# CONTROLLER_SCH.net
KiCad netlist of a schematic drawn in Altium Designer
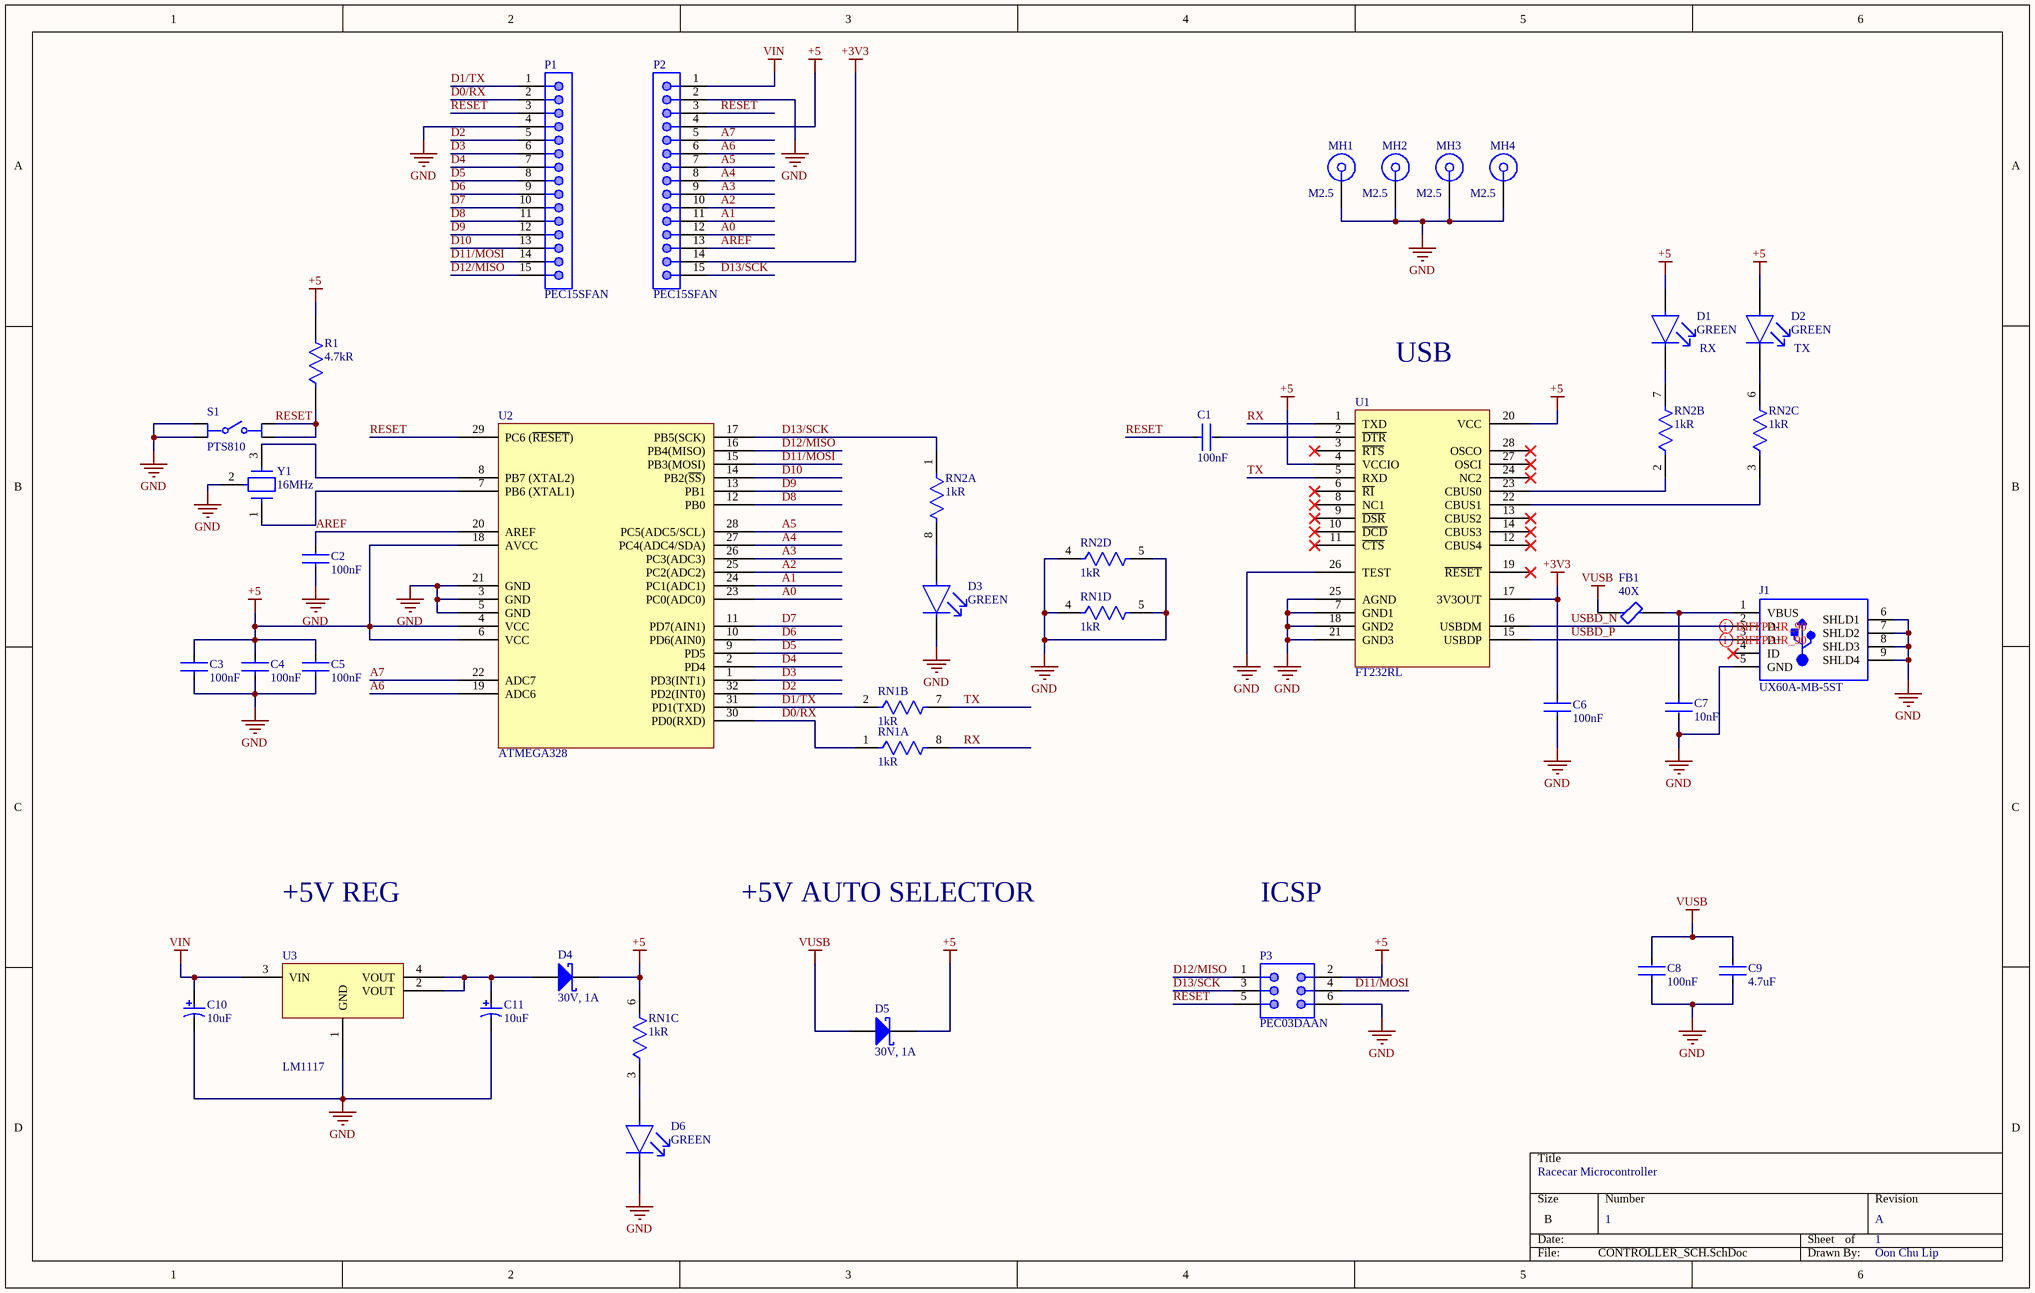
[diagram p0: CONTROLLER_SCH.SchDoc]

(export (version "E")
  (design (tool "Eeschema 10.0.6"))
  (components
    (comp (ref "C1")
      (value "100nF")
      (footprint "CAP_0603_TDK_CGA3")
      (description "±10% 50V Ceramic Capacitor X7R 0603 (1608 Metric)")
      (fields
        (field (name "MANUFACTURER") "TDK Corporation")
        (field (name "MANUFACTURER PART NUMBER") "CGA3E2X7R1H104K080AA")
      )
      (libsource (lib "CONTROLLER_INT_LIB") (part "CAP_100nF_10%_50V"))
    )
    (comp (ref "C2")
      (value "100nF")
      (footprint "CAP_0603_TDK_CGA3")
      (description "±10% 50V Ceramic Capacitor X7R 0603 (1608 Metric)")
      (fields
        (field (name "MANUFACTURER") "TDK Corporation")
        (field (name "MANUFACTURER PART NUMBER") "CGA3E2X7R1H104K080AA")
      )
      (libsource (lib "CONTROLLER_INT_LIB") (part "CAP_100nF_10%_50V"))
    )
    (comp (ref "C3")
      (value "100nF")
      (footprint "CAP_0603_TDK_CGA3")
      (description "±10% 50V Ceramic Capacitor X7R 0603 (1608 Metric)")
      (fields
        (field (name "MANUFACTURER") "TDK Corporation")
        (field (name "MANUFACTURER PART NUMBER") "CGA3E2X7R1H104K080AA")
      )
      (libsource (lib "CONTROLLER_INT_LIB") (part "CAP_100nF_10%_50V"))
    )
    (comp (ref "C4")
      (value "100nF")
      (footprint "CAP_0603_TDK_CGA3")
      (description "±10% 50V Ceramic Capacitor X7R 0603 (1608 Metric)")
      (fields
        (field (name "MANUFACTURER") "TDK Corporation")
        (field (name "MANUFACTURER PART NUMBER") "CGA3E2X7R1H104K080AA")
      )
      (libsource (lib "CONTROLLER_INT_LIB") (part "CAP_100nF_10%_50V"))
    )
    (comp (ref "C5")
      (value "100nF")
      (footprint "CAP_0603_TDK_CGA3")
      (description "±10% 50V Ceramic Capacitor X7R 0603 (1608 Metric)")
      (fields
        (field (name "MANUFACTURER") "TDK Corporation")
        (field (name "MANUFACTURER PART NUMBER") "CGA3E2X7R1H104K080AA")
      )
      (libsource (lib "CONTROLLER_INT_LIB") (part "CAP_100nF_10%_50V"))
    )
    (comp (ref "C6")
      (value "100nF")
      (footprint "CAP_0603_TDK_CGA3")
      (description "±10% 50V Ceramic Capacitor X7R 0603 (1608 Metric)")
      (fields
        (field (name "MANUFACTURER") "TDK Corporation")
        (field (name "MANUFACTURER PART NUMBER") "CGA3E2X7R1H104K080AA")
      )
      (libsource (lib "CONTROLLER_INT_LIB") (part "CAP_100nF_10%_50V"))
    )
    (comp (ref "C7")
      (value "10nF")
      (footprint "CAP_0603_MRT_GCM")
      (description "±10% 100V Ceramic Capacitor X7R 0603 (1608 Metric)")
      (fields
        (field (name "MANUFACTURER") "Murata Electronics")
        (field (name "MANUFACTURER PART NUMBER") "GCM188R72A103KA37D")
      )
      (libsource (lib "CONTROLLER_INT_LIB") (part "CAP_10nF_10%_100V"))
    )
    (comp (ref "C8")
      (value "100nF")
      (footprint "CAP_0603_TDK_CGA3")
      (description "±10% 50V Ceramic Capacitor X7R 0603 (1608 Metric)")
      (fields
        (field (name "MANUFACTURER") "TDK Corporation")
        (field (name "MANUFACTURER PART NUMBER") "CGA3E2X7R1H104K080AA")
      )
      (libsource (lib "CONTROLLER_INT_LIB") (part "CAP_100nF_10%_50V"))
    )
    (comp (ref "C9")
      (value "4.7uF")
      (footprint "CAP_0603_MRT_GRT")
      (description "±10% 25V Ceramic Capacitor X5R 0603 (1608 Metric)")
      (fields
        (field (name "MANUFACTURER") "Murata Electronics")
        (field (name "MANUFACTURER PART NUMBER") "GRT188R61E475KE13D")
      )
      (libsource (lib "CONTROLLER_INT_LIB") (part "CAP_4.7uF_10%_25V"))
    )
    (comp (ref "C10")
      (value "10uF")
      (footprint "PCAP_1411_VSH_TR3B")
      (description "Molded Tantalum Capacitors 1411 (3528 Metric) 1.1Ohm")
      (fields
        (field (name "MANUFACTURER") "Vishay Sprague")
        (field (name "MANUFACTURER PART NUMBER") "TR3B106K025C1100")
      )
      (libsource (lib "CONTROLLER_INT_LIB") (part "PCAP_10uF_10%_25V"))
    )
    (comp (ref "C11")
      (value "10uF")
      (footprint "PCAP_1411_VSH_TR3B")
      (description "Molded Tantalum Capacitors 1411 (3528 Metric) 1.1Ohm")
      (fields
        (field (name "MANUFACTURER") "Vishay Sprague")
        (field (name "MANUFACTURER PART NUMBER") "TR3B106K025C1100")
      )
      (libsource (lib "CONTROLLER_INT_LIB") (part "PCAP_10uF_10%_25V"))
    )
    (comp (ref "D1")
      (value "GREEN")
      (footprint "DIO_LED_GREEN_1608_APT1608")
      (description "Green 570nm LED Indication - Discrete 2.1V 0603 (1608 Metric)")
      (fields
        (field (name "MANUFACTURER") "Kingbright")
        (field (name "MANUFACTURER PART NUMBER") "APT1608CGCK")
      )
      (libsource (lib "CONTROLLER_INT_LIB") (part "DIO_LED_GREEN"))
    )
    (comp (ref "D2")
      (value "GREEN")
      (footprint "DIO_LED_GREEN_1608_APT1608")
      (description "Green 570nm LED Indication - Discrete 2.1V 0603 (1608 Metric)")
      (fields
        (field (name "MANUFACTURER") "Kingbright")
        (field (name "MANUFACTURER PART NUMBER") "APT1608CGCK")
      )
      (libsource (lib "CONTROLLER_INT_LIB") (part "DIO_LED_GREEN"))
    )
    (comp (ref "D3")
      (value "GREEN")
      (footprint "DIO_LED_GREEN_1608_APT1608")
      (description "Green 570nm LED Indication - Discrete 2.1V 0603 (1608 Metric)")
      (fields
        (field (name "MANUFACTURER") "Kingbright")
        (field (name "MANUFACTURER PART NUMBER") "APT1608CGCK")
      )
      (libsource (lib "CONTROLLER_INT_LIB") (part "DIO_LED_GREEN"))
    )
    (comp (ref "D4")
      (value "30V, 1A")
      (footprint "DIO_SCHOTTKY_DO_219AP")
      (description "Diode Schottky 1A Surface Mount MicroSMP (DO-219AD)")
      (fields
        (field (name "MANUFACTURER") "Vishay General Semiconductor - Diodes Division")
        (field (name "MANUFACTURER PART NUMBER") "MSS1P3L-M3/89A")
      )
      (libsource (lib "CONTROLLER_INT_LIB") (part "DIO_SCHOTTKY_30V_1A"))
    )
    (comp (ref "D5")
      (value "30V, 1A")
      (footprint "DIO_SCHOTTKY_DO_219AP")
      (description "Diode Schottky 1A Surface Mount MicroSMP (DO-219AD)")
      (fields
        (field (name "MANUFACTURER") "Vishay General Semiconductor - Diodes Division")
        (field (name "MANUFACTURER PART NUMBER") "MSS1P3L-M3/89A")
      )
      (libsource (lib "CONTROLLER_INT_LIB") (part "DIO_SCHOTTKY_30V_1A"))
    )
    (comp (ref "D6")
      (value "GREEN")
      (footprint "DIO_LED_GREEN_1608_APT1608")
      (description "Green 570nm LED Indication - Discrete 2.1V 0603 (1608 Metric)")
      (fields
        (field (name "MANUFACTURER") "Kingbright")
        (field (name "MANUFACTURER PART NUMBER") "APT1608CGCK")
      )
      (libsource (lib "CONTROLLER_INT_LIB") (part "DIO_LED_GREEN"))
    )
    (comp (ref "FB1")
      (value "40X")
      (footprint "FERRITE_0805_LRD_MI")
      (description "Power Line Ferrite Bead 0805 (2012 Metric) 1.5A 50mOhm")
      (fields
        (field (name "MANUFACTURER") "Laird-Signal Integrity Products")
        (field (name "MANUFACTURER PART NUMBER") "MI0805K400R-10")
      )
      (libsource (lib "CONTROLLER_INT_LIB") (part "FERRITE_40X_1.5A"))
    )
    (comp (ref "J1")
      (value "UX60A-MB-5ST")
      (footprint "CONN_USB_MINIB_FEMALE_SMD_RA")
      (description "USB - mini B USB 2.0 Receptacle Connector 5 Position Surface Mount, Right Angle")
      (fields (field (name "MANUFACTURER") "Hirose Electric Co LtdInc."))
      (libsource (lib "CONTROLLER_INT_LIB") (part "CONN_USB_MINIB_FEMALE_SMD_RA"))
    )
    (comp (ref "MH1")
      (value "M2.5")
      (footprint "MH_M2.5")
      (description "M2.5 Mounting Hole")
      (libsource (lib "CONTROLLER_INT_LIB") (part "MH_M2.5"))
    )
    (comp (ref "MH2")
      (value "M2.5")
      (footprint "MH_M2.5")
      (description "M2.5 Mounting Hole")
      (libsource (lib "CONTROLLER_INT_LIB") (part "MH_M2.5"))
    )
    (comp (ref "MH3")
      (value "M2.5")
      (footprint "MH_M2.5")
      (description "M2.5 Mounting Hole")
      (libsource (lib "CONTROLLER_INT_LIB") (part "MH_M2.5"))
    )
    (comp (ref "MH4")
      (value "M2.5")
      (footprint "MH_M2.5")
      (description "M2.5 Mounting Hole")
      (libsource (lib "CONTROLLER_INT_LIB") (part "MH_M2.5"))
    )
    (comp (ref "P1")
      (value "PEC15SFAN")
      (footprint "CONN_HEADER_MALE_0.1_1x15")
      (description "Connector Header Through Hole 15 position 0.100\" (2.54mm)")
      (fields (field (name "MANUFACTURER") "Sullins Connector Solutions"))
      (libsource (lib "") (part "CONN_VERT_HEADER_MALE_0.1_1x15_1"))
    )
    (comp (ref "P2")
      (value "PEC15SFAN")
      (footprint "CONN_HEADER_MALE_0.1_1x15")
      (description "Connector Header Through Hole 15 position 0.100\" (2.54mm)")
      (fields (field (name "MANUFACTURER") "Sullins Connector Solutions"))
      (libsource (lib "CONTROLLER_INT_LIB") (part "CONN_VERT_HEADER_MALE_0.1_1x15"))
    )
    (comp (ref "P3")
      (value "PEC03DAAN")
      (footprint "CONN_HEADER_MALE_0.1_2x3")
      (description "Connector Header Through Hole 6 position 0.100\" (2.54mm)")
      (fields (field (name "MANUFACTURER") "Sullins Connector Solutions"))
      (libsource (lib "CONTROLLER_INT_LIB") (part "CONN_VERT_HEADER_MALE_0.1_2x3"))
    )
    (comp (ref "R1")
      (value "4.7kR")
      (footprint "RES_0603_RHM_ESR")
      (fields
        (field (name "MANUFACTURER") "Rohm Semiconductor")
        (field (name "MANUFACTURER PART NUMBER") "ESR03EZPJ472")
      )
      (libsource (lib "CONTROLLER_INT_LIB") (part "RES_4.7kR_5%_0.25W"))
    )
    (comp (ref "RN1")
      (value "1kR")
      (footprint "RES_NET_0502_PNS_EXB")
      (fields
        (field (name "MANUFACTURER") "Panasonic Electronic Components")
        (field (name "MANUFACTURER PART NUMBER") "EXB-18V102JX")
      )
      (libsource (lib "CONTROLLER_INT_LIB") (part "RES_NET_1kR_5%_31mW"))
    )
    (comp (ref "RN2")
      (value "1kR")
      (footprint "RES_NET_0502_PNS_EXB")
      (fields
        (field (name "MANUFACTURER") "Panasonic Electronic Components")
        (field (name "MANUFACTURER PART NUMBER") "EXB-18V102JX")
      )
      (libsource (lib "CONTROLLER_INT_LIB") (part "RES_NET_1kR_5%_31mW"))
    )
    (comp (ref "S1")
      (value "PTS810")
      (footprint "SW_CAK_PTS810")
      (description "Tactile Switch SPST-NO Top Actuated Surface Mount")
      (fields
        (field (name "MANUFACTURER") "C&K")
        (field (name "MANUFACTURER PART NUMBER") "PTS810 SJG 250 SMTR LFS")
      )
      (libsource (lib "CONTROLLER_INT_LIB") (part "SW_SPST_NO"))
    )
    (comp (ref "U1")
      (value "FT232RL")
      (footprint "IC_SSOP_28")
      (description "USB Bridge, USB to UART USB 2.0 UART Interface 28-SSOP")
      (fields
        (field (name "MANUFACTURER") "FTDI, Future Technology Devices International Ltd")
        (field (name "MANUFACTURER PART NUMBER") "FT232RL-REEL")
      )
      (libsource (lib "CONTROLLER_INT_LIB") (part "IC_FT232RL"))
    )
    (comp (ref "U2")
      (value "ATMEGA328")
      (footprint "IC_32_TQFP_32A")
      (description "8-bit Microcontrollers - MCU AVR 32K FLSH 2K SRAM 1KB EE-20 MHZ 105C")
      (fields
        (field (name "MANUFACTURER") "Microchip Technology / Atmel")
        (field (name "MANUFACTURER PART NUMBER") "ATMEGA328P-AN")
      )
      (libsource (lib "CONTROLLER_INT_LIB") (part "IC_ATMEGA328"))
    )
    (comp (ref "U3")
      (value "LM1117")
      (footprint "IC_SOT223_4_DCYRPDSOG4")
      (description "Linear Voltage Regulator IC Positive Fixed Output 800mA SOT-223-4")
      (fields
        (field (name "MANUFACTURER") "Texas Instruments")
        (field (name "MANUFACTURER PART NUMBER") "LM1117IMPX-5.0/NOPB")
      )
      (libsource (lib "CONTROLLER_INT_LIB") (part "IC_LM1117"))
    )
    (comp (ref "Y1")
      (value "16MHz")
      (footprint "OSC_NONSTD_SMD3_MRT_CSTNE")
      (description "Ceramic Resonator Built in Capacitor ±0.15% -40°C ~ 125°C Surface Mount")
      (fields
        (field (name "MANUFACTURER") "Murata Electronics")
        (field (name "MANUFACTURER PART NUMBER") "CSTNE16M0V53C000R0")
      )
      (libsource (lib "CONTROLLER_INT_LIB") (part "OSC_CER_16MHz"))
    )
  )
  (nets
    (net (code "1") (name "+3V3") (class "Default")
      (node (ref "C6") (pin "2") (pinfunction "2_2") (pintype "passive"))
      (node (ref "P2") (pin "14") (pinfunction "14_14") (pintype "passive"))
      (node (ref "U1") (pin "17") (pinfunction "3V3OUT_17") (pintype "passive"))
    )
    (net (code "2") (name "+5") (class "Default")
      (node (ref "C3") (pin "2") (pinfunction "2_2") (pintype "passive"))
      (node (ref "C4") (pin "2") (pinfunction "2_2") (pintype "passive"))
      (node (ref "C5") (pin "2") (pinfunction "2_2") (pintype "passive"))
      (node (ref "D1") (pin "2") (pinfunction "2_2") (pintype "passive"))
      (node (ref "D2") (pin "2") (pinfunction "2_2") (pintype "passive"))
      (node (ref "D4") (pin "K") (pinfunction "K_K") (pintype "passive"))
      (node (ref "D5") (pin "K") (pinfunction "K_K") (pintype "passive"))
      (node (ref "P2") (pin "4") (pinfunction "4_4") (pintype "passive"))
      (node (ref "P3") (pin "2") (pinfunction "2_2") (pintype "passive"))
      (node (ref "R1") (pin "2") (pinfunction "2_2") (pintype "passive"))
      (node (ref "RN1") (pin "6") (pinfunction "6_6") (pintype "passive"))
      (node (ref "U1") (pin "20") (pinfunction "VCC_20") (pintype "passive"))
      (node (ref "U1") (pin "4") (pinfunction "VCCIO_4") (pintype "passive"))
      (node (ref "U2") (pin "18") (pinfunction "AVCC_18") (pintype "passive"))
      (node (ref "U2") (pin "4") (pinfunction "VCC_4") (pintype "passive"))
      (node (ref "U2") (pin "6") (pinfunction "VCC_6") (pintype "passive"))
    )
    (net (code "3") (name "/A0") (class "Default")
      (node (ref "P2") (pin "12") (pinfunction "12_12") (pintype "passive"))
      (node (ref "U2") (pin "23") (pinfunction "PC0(ADC0)_23") (pintype "passive"))
    )
    (net (code "4") (name "/A1") (class "Default")
      (node (ref "P2") (pin "11") (pinfunction "11_11") (pintype "passive"))
      (node (ref "U2") (pin "24") (pinfunction "PC1(ADC1)_24") (pintype "passive"))
    )
    (net (code "5") (name "/A2") (class "Default")
      (node (ref "P2") (pin "10") (pinfunction "10_10") (pintype "passive"))
      (node (ref "U2") (pin "25") (pinfunction "PC2(ADC2)_25") (pintype "passive"))
    )
    (net (code "6") (name "/A3") (class "Default")
      (node (ref "P2") (pin "9") (pinfunction "9_9") (pintype "passive"))
      (node (ref "U2") (pin "26") (pinfunction "PC3(ADC3)_26") (pintype "passive"))
    )
    (net (code "7") (name "/A4") (class "Default")
      (node (ref "P2") (pin "8") (pinfunction "8_8") (pintype "passive"))
      (node (ref "U2") (pin "27") (pinfunction "PC4(ADC4/SDA)_27") (pintype "passive"))
    )
    (net (code "8") (name "/A5") (class "Default")
      (node (ref "P2") (pin "7") (pinfunction "7_7") (pintype "passive"))
      (node (ref "U2") (pin "28") (pinfunction "PC5(ADC5/SCL)_28") (pintype "passive"))
    )
    (net (code "9") (name "/A6") (class "Default")
      (node (ref "P2") (pin "6") (pinfunction "6_6") (pintype "passive"))
      (node (ref "U2") (pin "19") (pinfunction "ADC6_19") (pintype "passive"))
    )
    (net (code "10") (name "/A7") (class "Default")
      (node (ref "P2") (pin "5") (pinfunction "6_5") (pintype "passive"))
      (node (ref "U2") (pin "22") (pinfunction "ADC7_22") (pintype "passive"))
    )
    (net (code "11") (name "/AREF") (class "Default")
      (node (ref "C2") (pin "2") (pinfunction "2_2") (pintype "passive"))
      (node (ref "P2") (pin "13") (pinfunction "13_13") (pintype "passive"))
      (node (ref "U2") (pin "20") (pinfunction "AREF_20") (pintype "passive"))
    )
    (net (code "12") (name "/D0{slash}RX") (class "Default")
      (node (ref "P1") (pin "2") (pinfunction "2_2") (pintype "passive"))
      (node (ref "RN1") (pin "1") (pinfunction "1_1") (pintype "passive"))
      (node (ref "U2") (pin "30") (pinfunction "PD0(RXD)_30") (pintype "passive"))
    )
    (net (code "13") (name "/D1{slash}TX") (class "Default")
      (node (ref "P1") (pin "1") (pinfunction "1_1") (pintype "passive"))
      (node (ref "RN1") (pin "2") (pinfunction "2_2") (pintype "passive"))
      (node (ref "U2") (pin "31") (pinfunction "PD1(TXD)_31") (pintype "passive"))
    )
    (net (code "14") (name "/D2") (class "Default")
      (node (ref "P1") (pin "5") (pinfunction "6_5") (pintype "passive"))
      (node (ref "U2") (pin "32") (pinfunction "PD2(INT0)_32") (pintype "passive"))
    )
    (net (code "15") (name "/D3") (class "Default")
      (node (ref "P1") (pin "6") (pinfunction "6_6") (pintype "passive"))
      (node (ref "U2") (pin "1") (pinfunction "PD3(INT1)_1") (pintype "passive"))
    )
    (net (code "16") (name "/D4") (class "Default")
      (node (ref "P1") (pin "7") (pinfunction "7_7") (pintype "passive"))
      (node (ref "U2") (pin "2") (pinfunction "PD4_2") (pintype "passive"))
    )
    (net (code "17") (name "/D5") (class "Default")
      (node (ref "P1") (pin "8") (pinfunction "8_8") (pintype "passive"))
      (node (ref "U2") (pin "9") (pinfunction "PD5_9") (pintype "passive"))
    )
    (net (code "18") (name "/D6") (class "Default")
      (node (ref "P1") (pin "9") (pinfunction "9_9") (pintype "passive"))
      (node (ref "U2") (pin "10") (pinfunction "PD6(AIN0)_10") (pintype "passive"))
    )
    (net (code "19") (name "/D7") (class "Default")
      (node (ref "P1") (pin "10") (pinfunction "10_10") (pintype "passive"))
      (node (ref "U2") (pin "11") (pinfunction "PD7(AIN1)_11") (pintype "passive"))
    )
    (net (code "20") (name "/D8") (class "Default")
      (node (ref "P1") (pin "11") (pinfunction "11_11") (pintype "passive"))
      (node (ref "U2") (pin "12") (pinfunction "PB0_12") (pintype "passive"))
    )
    (net (code "21") (name "/D9") (class "Default")
      (node (ref "P1") (pin "12") (pinfunction "12_12") (pintype "passive"))
      (node (ref "U2") (pin "13") (pinfunction "PB1_13") (pintype "passive"))
    )
    (net (code "22") (name "/D10") (class "Default")
      (node (ref "P1") (pin "13") (pinfunction "13_13") (pintype "passive"))
      (node (ref "U2") (pin "14") (pinfunction "PB2(~{SS})_14") (pintype "passive"))
    )
    (net (code "23") (name "/D11{slash}MOSI") (class "Default")
      (node (ref "P1") (pin "14") (pinfunction "14_14") (pintype "passive"))
      (node (ref "P3") (pin "4") (pinfunction "4_4") (pintype "passive"))
      (node (ref "U2") (pin "15") (pinfunction "PB3(MOSI)_15") (pintype "passive"))
    )
    (net (code "24") (name "/D12{slash}MISO") (class "Default")
      (node (ref "P1") (pin "15") (pinfunction "15_15") (pintype "passive"))
      (node (ref "P3") (pin "1") (pinfunction "1_1") (pintype "passive"))
      (node (ref "U2") (pin "16") (pinfunction "PB4(MISO)_16") (pintype "passive"))
    )
    (net (code "25") (name "/D13{slash}SCK") (class "Default")
      (node (ref "P2") (pin "15") (pinfunction "15_15") (pintype "passive"))
      (node (ref "P3") (pin "3") (pinfunction "3_3") (pintype "passive"))
      (node (ref "RN2") (pin "1") (pinfunction "1_1") (pintype "passive"))
      (node (ref "U2") (pin "17") (pinfunction "PB5(SCK)_17") (pintype "passive"))
    )
    (net (code "26") (name "/RESET") (class "Default")
      (node (ref "C1") (pin "1") (pinfunction "1_1") (pintype "passive"))
      (node (ref "P1") (pin "3") (pinfunction "3_3") (pintype "passive"))
      (node (ref "P2") (pin "3") (pinfunction "3_3") (pintype "passive"))
      (node (ref "P3") (pin "5") (pinfunction "5_5") (pintype "passive"))
      (node (ref "R1") (pin "1") (pinfunction "1_1") (pintype "passive"))
      (node (ref "S1") (pin "3") (pinfunction "3_3") (pintype "passive"))
      (node (ref "S1") (pin "4") (pinfunction "4_4") (pintype "passive"))
      (node (ref "U2") (pin "29") (pinfunction "PC6_(~{RESET})_29") (pintype "passive"))
    )
    (net (code "27") (name "/RX") (class "Default")
      (node (ref "RN1") (pin "8") (pinfunction "8_8") (pintype "passive"))
      (node (ref "U1") (pin "1") (pinfunction "TXD_1") (pintype "passive"))
    )
    (net (code "28") (name "/TX") (class "Default")
      (node (ref "RN1") (pin "7") (pinfunction "7_7") (pintype "passive"))
      (node (ref "U1") (pin "5") (pinfunction "RXD_5") (pintype "passive"))
    )
    (net (code "29") (name "/USBD_N") (class "Default")
      (node (ref "J1") (pin "2") (pinfunction "D-_2") (pintype "passive"))
      (node (ref "U1") (pin "16") (pinfunction "USBDM_16") (pintype "passive"))
    )
    (net (code "30") (name "/USBD_P") (class "Default")
      (node (ref "J1") (pin "3") (pinfunction "D+_3") (pintype "passive"))
      (node (ref "U1") (pin "15") (pinfunction "USBDP_15") (pintype "passive"))
    )
    (net (code "31") (name "GND") (class "Default")
      (node (ref "C10") (pin "2") (pinfunction "2_2") (pintype "passive"))
      (node (ref "C11") (pin "2") (pinfunction "2_2") (pintype "passive"))
      (node (ref "C2") (pin "1") (pinfunction "1_1") (pintype "passive"))
      (node (ref "C3") (pin "1") (pinfunction "1_1") (pintype "passive"))
      (node (ref "C4") (pin "1") (pinfunction "1_1") (pintype "passive"))
      (node (ref "C5") (pin "1") (pinfunction "1_1") (pintype "passive"))
      (node (ref "C6") (pin "1") (pinfunction "1_1") (pintype "passive"))
      (node (ref "C7") (pin "2") (pinfunction "2_2") (pintype "passive"))
      (node (ref "C8") (pin "1") (pinfunction "1_1") (pintype "passive"))
      (node (ref "C9") (pin "1") (pinfunction "1_1") (pintype "passive"))
      (node (ref "D3") (pin "1") (pinfunction "1_1") (pintype "passive"))
      (node (ref "D6") (pin "1") (pinfunction "1_1") (pintype "passive"))
      (node (ref "J1") (pin "5") (pinfunction "GND_5") (pintype "passive"))
      (node (ref "J1") (pin "6") (pinfunction "SHLD1_6") (pintype "passive"))
      (node (ref "J1") (pin "7") (pinfunction "SHLD2_7") (pintype "passive"))
      (node (ref "J1") (pin "8") (pinfunction "SHLD3_8") (pintype "passive"))
      (node (ref "J1") (pin "9") (pinfunction "SHLD4_9") (pintype "passive"))
      (node (ref "MH1") (pin "1") (pinfunction "1_1") (pintype "passive"))
      (node (ref "MH2") (pin "1") (pinfunction "1_1") (pintype "passive"))
      (node (ref "MH3") (pin "1") (pinfunction "1_1") (pintype "passive"))
      (node (ref "MH4") (pin "1") (pinfunction "1_1") (pintype "passive"))
      (node (ref "P1") (pin "4") (pinfunction "4_4") (pintype "passive"))
      (node (ref "P2") (pin "2") (pinfunction "2_2") (pintype "passive"))
      (node (ref "P3") (pin "6") (pinfunction "6_6") (pintype "passive"))
      (node (ref "RN1") (pin "4") (pinfunction "4_4") (pintype "passive"))
      (node (ref "RN1") (pin "5") (pinfunction "5_5") (pintype "passive"))
      (node (ref "RN2") (pin "4") (pinfunction "4_4") (pintype "passive"))
      (node (ref "RN2") (pin "5") (pinfunction "5_5") (pintype "passive"))
      (node (ref "S1") (pin "1") (pinfunction "1_1") (pintype "passive"))
      (node (ref "S1") (pin "2") (pinfunction "2_2") (pintype "passive"))
      (node (ref "U1") (pin "18") (pinfunction "GND2_18") (pintype "passive"))
      (node (ref "U1") (pin "21") (pinfunction "GND3_21") (pintype "passive"))
      (node (ref "U1") (pin "25") (pinfunction "AGND_25") (pintype "passive"))
      (node (ref "U1") (pin "26") (pinfunction "TEST_26") (pintype "passive"))
      (node (ref "U1") (pin "7") (pinfunction "GND1_7") (pintype "passive"))
      (node (ref "U2") (pin "21") (pinfunction "GND_21") (pintype "passive"))
      (node (ref "U2") (pin "3") (pinfunction "GND_3") (pintype "passive"))
      (node (ref "U2") (pin "5") (pinfunction "GND_5") (pintype "passive"))
      (node (ref "U3") (pin "1") (pinfunction "GND_1") (pintype "passive"))
      (node (ref "Y1") (pin "2") (pinfunction "GND_2") (pintype "power_in"))
    )
    (net (code "32") (name "Net-(C11-Pad1)") (class "Default")
      (node (ref "C11") (pin "1") (pinfunction "1_1") (pintype "passive"))
      (node (ref "D4") (pin "A") (pinfunction "A_A") (pintype "passive"))
      (node (ref "U3") (pin "2") (pinfunction "VOUT_2") (pintype "passive"))
      (node (ref "U3") (pin "4") (pinfunction "VOUT_4") (pintype "passive"))
    )
    (net (code "33") (name "Net-(D1-Pad1)") (class "Default")
      (node (ref "D1") (pin "1") (pinfunction "1_1") (pintype "passive"))
      (node (ref "RN2") (pin "7") (pinfunction "7_7") (pintype "passive"))
    )
    (net (code "34") (name "Net-(D2-Pad1)") (class "Default")
      (node (ref "D2") (pin "1") (pinfunction "1_1") (pintype "passive"))
      (node (ref "RN2") (pin "6") (pinfunction "6_6") (pintype "passive"))
    )
    (net (code "35") (name "Net-(D3-Pad2)") (class "Default")
      (node (ref "D3") (pin "2") (pinfunction "2_2") (pintype "passive"))
      (node (ref "RN2") (pin "8") (pinfunction "8_8") (pintype "passive"))
    )
    (net (code "36") (name "Net-(D6-Pad2)") (class "Default")
      (node (ref "D6") (pin "2") (pinfunction "2_2") (pintype "passive"))
      (node (ref "RN1") (pin "3") (pinfunction "3_3") (pintype "passive"))
    )
    (net (code "37") (name "Net-(J1-VBUS)") (class "Default")
      (node (ref "C7") (pin "1") (pinfunction "1_1") (pintype "passive"))
      (node (ref "FB1") (pin "2") (pinfunction "2_2") (pintype "passive"))
      (node (ref "J1") (pin "1") (pinfunction "VBUS_1") (pintype "passive"))
    )
    (net (code "38") (name "Net-(U1-CBUS0)") (class "Default")
      (node (ref "RN2") (pin "2") (pinfunction "2_2") (pintype "passive"))
      (node (ref "U1") (pin "23") (pinfunction "CBUS0_23") (pintype "passive"))
    )
    (net (code "39") (name "Net-(U1-CBUS1)") (class "Default")
      (node (ref "RN2") (pin "3") (pinfunction "3_3") (pintype "passive"))
      (node (ref "U1") (pin "22") (pinfunction "CBUS1_22") (pintype "passive"))
    )
    (net (code "40") (name "Net-(U1-DTR)") (class "Default")
      (node (ref "C1") (pin "2") (pinfunction "2_2") (pintype "passive"))
      (node (ref "U1") (pin "2") (pinfunction "DTR_2") (pintype "passive"))
    )
    (net (code "41") (name "Net-(U2-PB6_(XTAL1))") (class "Default")
      (node (ref "U2") (pin "7") (pinfunction "PB6_(XTAL1)_7") (pintype "passive"))
      (node (ref "Y1") (pin "1") (pinfunction "Input_1") (pintype "passive"))
    )
    (net (code "42") (name "Net-(U2-PB7_(XTAL2))") (class "Default")
      (node (ref "U2") (pin "8") (pinfunction "PB7_(XTAL2)_8") (pintype "passive"))
      (node (ref "Y1") (pin "3") (pinfunction "Output_3") (pintype "passive"))
    )
    (net (code "43") (name "VIN") (class "Default")
      (node (ref "C10") (pin "1") (pinfunction "1_1") (pintype "passive"))
      (node (ref "P2") (pin "1") (pinfunction "1_1") (pintype "passive"))
      (node (ref "U3") (pin "3") (pinfunction "VIN_3") (pintype "passive"))
    )
    (net (code "44") (name "VUSB") (class "Default")
      (node (ref "C8") (pin "2") (pinfunction "2_2") (pintype "passive"))
      (node (ref "C9") (pin "2") (pinfunction "2_2") (pintype "passive"))
      (node (ref "D5") (pin "A") (pinfunction "A_A") (pintype "passive"))
      (node (ref "FB1") (pin "1") (pinfunction "1_1") (pintype "passive"))
    )
    (net (code "45") (name "unconnected-(J1-ID-Pad4)") (class "Default")
      (node (ref "J1") (pin "4") (pinfunction "ID_4") (pintype "passive+no_connect"))
    )
    (net (code "46") (name "unconnected-(U1-CBUS2-Pad13)") (class "Default")
      (node (ref "U1") (pin "13") (pinfunction "CBUS2_13") (pintype "passive+no_connect"))
    )
    (net (code "47") (name "unconnected-(U1-CBUS3-Pad14)") (class "Default")
      (node (ref "U1") (pin "14") (pinfunction "CBUS3_14") (pintype "passive+no_connect"))
    )
    (net (code "48") (name "unconnected-(U1-CBUS4-Pad12)") (class "Default")
      (node (ref "U1") (pin "12") (pinfunction "CBUS4_12") (pintype "passive+no_connect"))
    )
    (net (code "49") (name "unconnected-(U1-CTS-Pad11)") (class "Default")
      (node (ref "U1") (pin "11") (pinfunction "CTS_11") (pintype "passive+no_connect"))
    )
    (net (code "50") (name "unconnected-(U1-DCD-Pad10)") (class "Default")
      (node (ref "U1") (pin "10") (pinfunction "DCD_10") (pintype "passive+no_connect"))
    )
    (net (code "51") (name "unconnected-(U1-DSR-Pad9)") (class "Default")
      (node (ref "U1") (pin "9") (pinfunction "DSR_9") (pintype "passive+no_connect"))
    )
    (net (code "52") (name "unconnected-(U1-NC1-Pad8)") (class "Default")
      (node (ref "U1") (pin "8") (pinfunction "NC1_8") (pintype "passive+no_connect"))
    )
    (net (code "53") (name "unconnected-(U1-NC2-Pad24)") (class "Default")
      (node (ref "U1") (pin "24") (pinfunction "NC2_24") (pintype "passive+no_connect"))
    )
    (net (code "54") (name "unconnected-(U1-OSCI-Pad27)") (class "Default")
      (node (ref "U1") (pin "27") (pinfunction "OSCI_27") (pintype "passive+no_connect"))
    )
    (net (code "55") (name "unconnected-(U1-OSCO-Pad28)") (class "Default")
      (node (ref "U1") (pin "28") (pinfunction "OSCO_28") (pintype "passive+no_connect"))
    )
    (net (code "56") (name "unconnected-(U1-RESET-Pad19)") (class "Default")
      (node (ref "U1") (pin "19") (pinfunction "RESET_19") (pintype "passive+no_connect"))
    )
    (net (code "57") (name "unconnected-(U1-RI-Pad6)") (class "Default")
      (node (ref "U1") (pin "6") (pinfunction "RI_6") (pintype "passive+no_connect"))
    )
    (net (code "58") (name "unconnected-(U1-RTS-Pad3)") (class "Default")
      (node (ref "U1") (pin "3") (pinfunction "RTS_3") (pintype "passive+no_connect"))
    )
  )
)
